# Sheet_2.net
KiCad netlist of a schematic drawn in EasyEDA
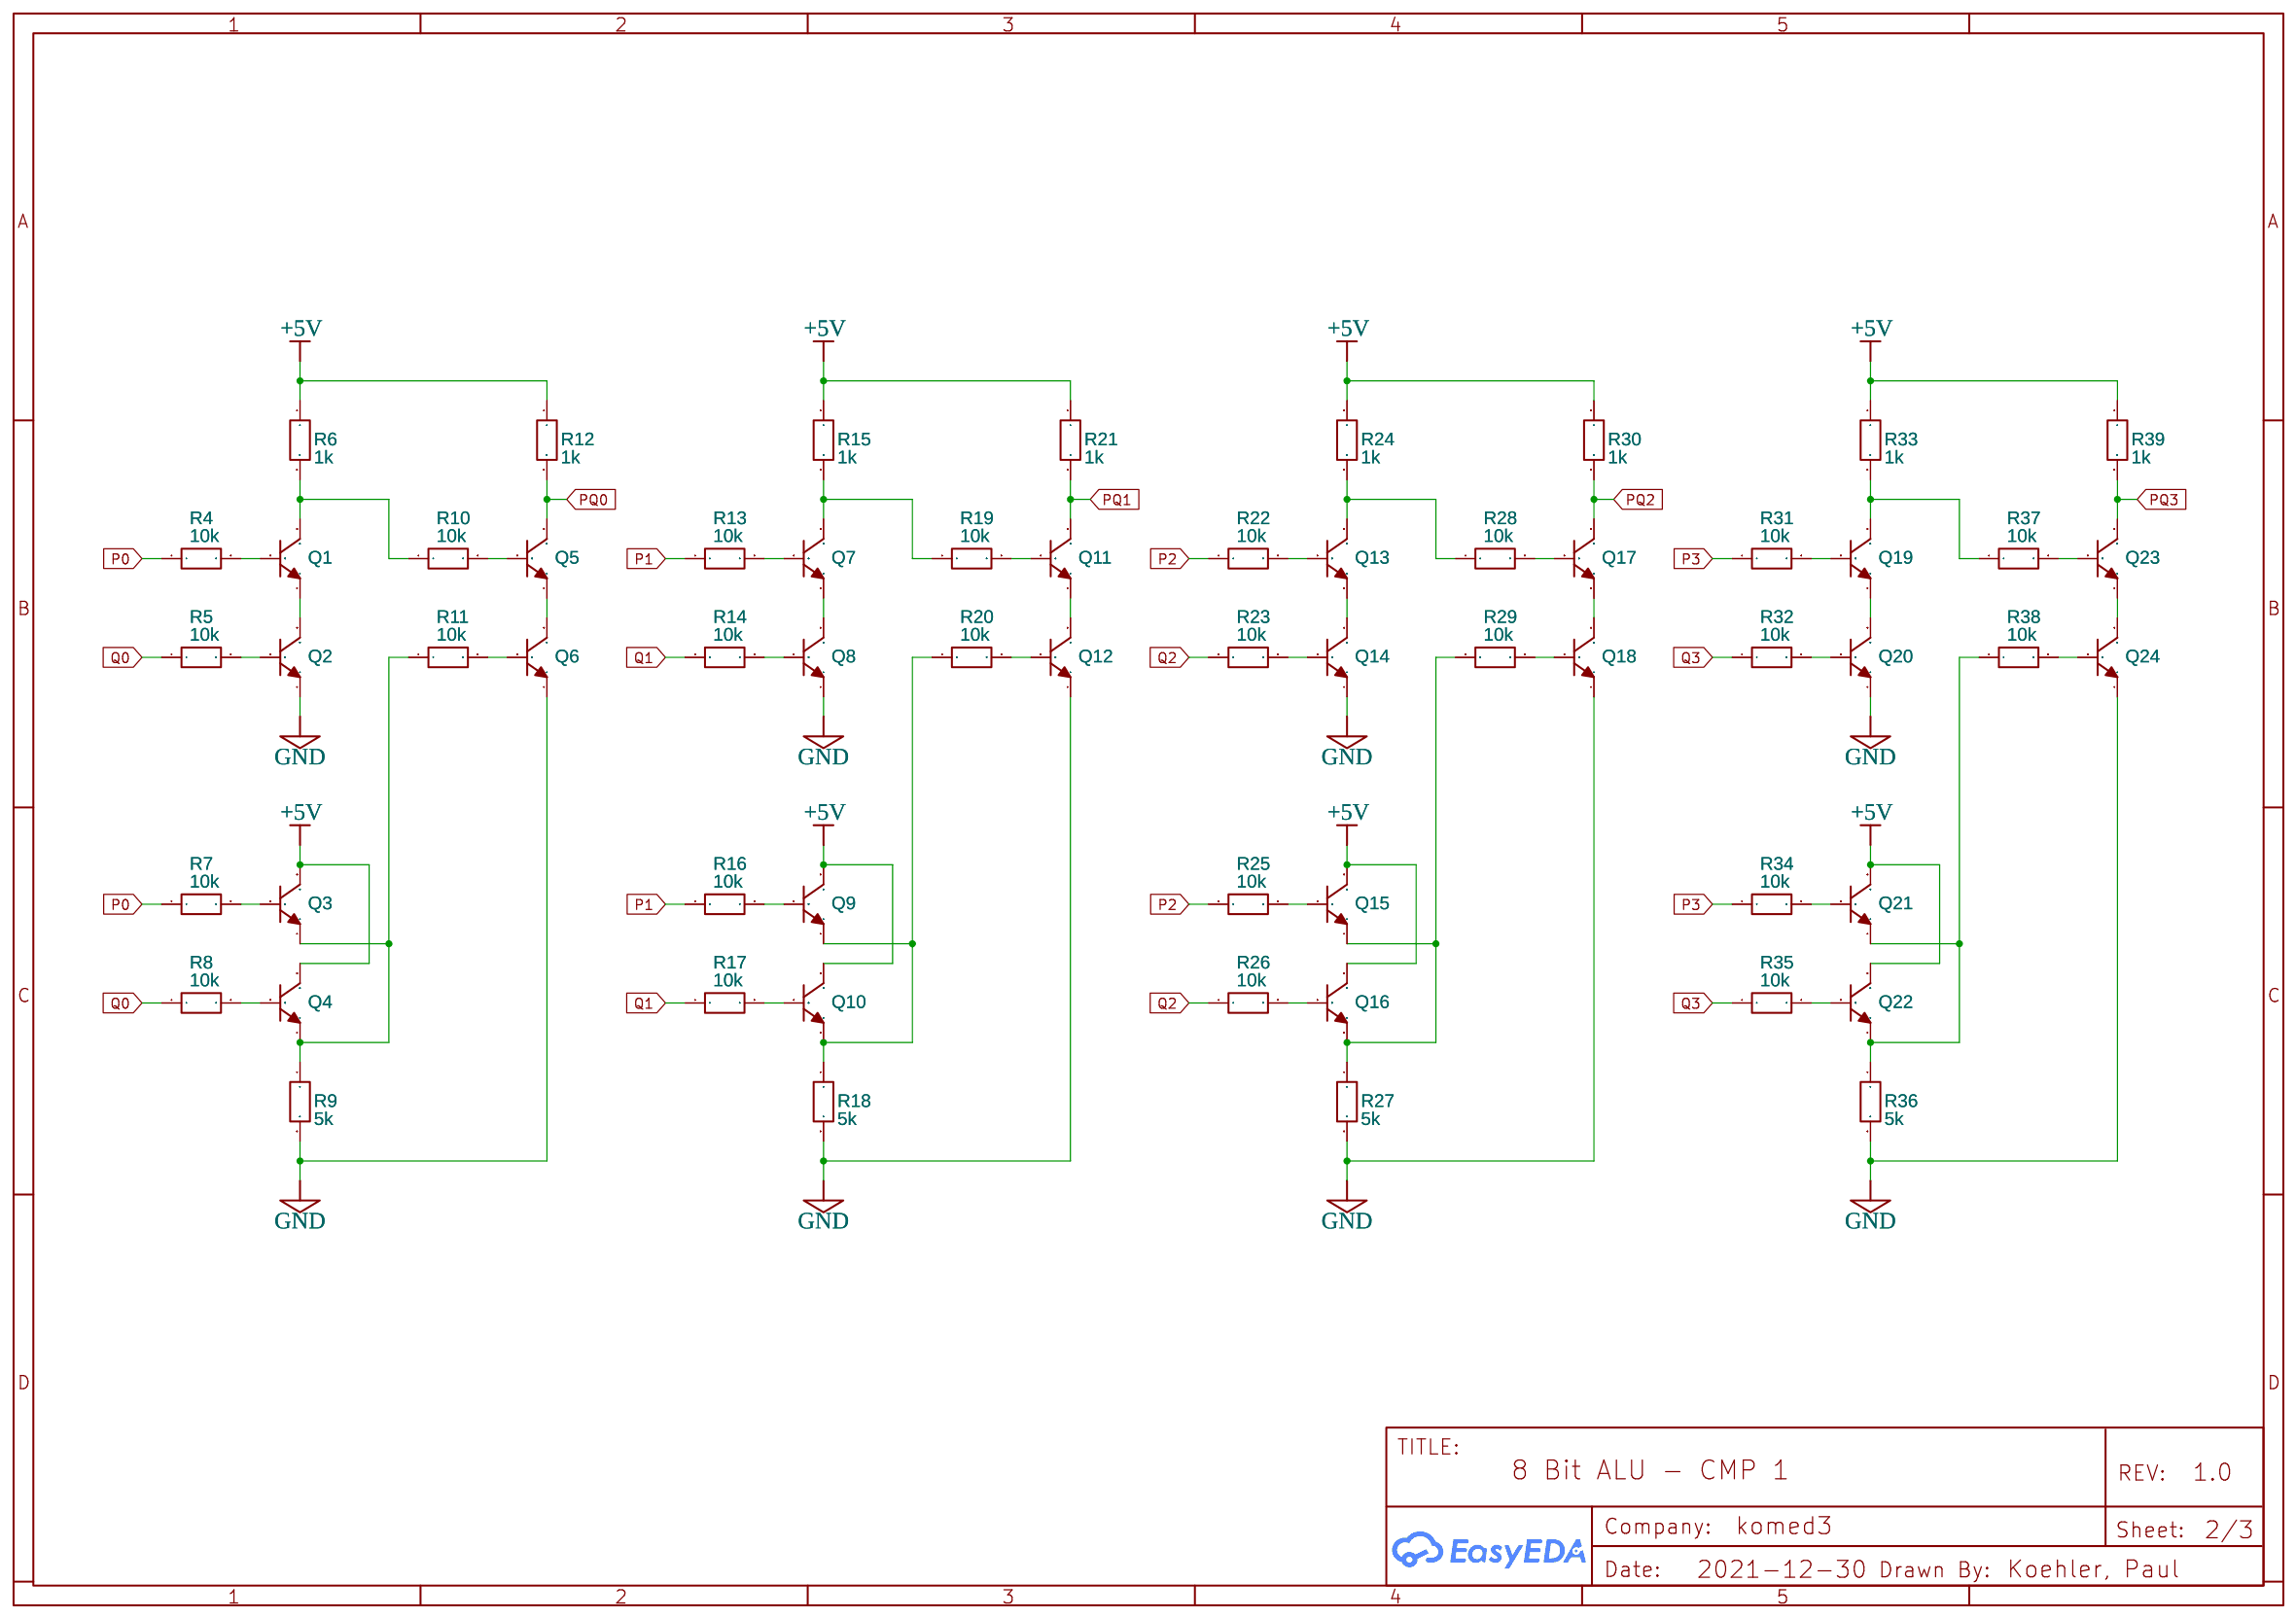
[diagram p0: schematic sheet]

(export (version "E")
  (design (tool "Eeschema 10.0.6"))
  (components
    (comp (ref "Q1")
      (value "2N3904(TO-92)")
      (fields (field (name "BOM_Manufacturer Part") "2N3904") (field (name "BOM_Supplier Part") "C118538"))
      (libsource (lib "") (part "2N3904(TO-92)"))
    )
    (comp (ref "Q2")
      (value "2N3904(TO-92)")
      (fields (field (name "BOM_Manufacturer Part") "2N3904") (field (name "BOM_Supplier Part") "C118538"))
      (libsource (lib "") (part "2N3904(TO-92)"))
    )
    (comp (ref "Q3")
      (value "2N3904(TO-92)")
      (fields (field (name "BOM_Manufacturer Part") "2N3904") (field (name "BOM_Supplier Part") "C118538"))
      (libsource (lib "") (part "2N3904(TO-92)"))
    )
    (comp (ref "Q4")
      (value "2N3904(TO-92)")
      (fields (field (name "BOM_Manufacturer Part") "2N3904") (field (name "BOM_Supplier Part") "C118538"))
      (libsource (lib "") (part "2N3904(TO-92)"))
    )
    (comp (ref "Q5")
      (value "2N3904(TO-92)")
      (fields (field (name "BOM_Manufacturer Part") "2N3904") (field (name "BOM_Supplier Part") "C118538"))
      (libsource (lib "") (part "2N3904(TO-92)"))
    )
    (comp (ref "Q6")
      (value "2N3904(TO-92)")
      (fields (field (name "BOM_Manufacturer Part") "2N3904") (field (name "BOM_Supplier Part") "C118538"))
      (libsource (lib "") (part "2N3904(TO-92)"))
    )
    (comp (ref "Q7")
      (value "2N3904(TO-92)")
      (fields (field (name "BOM_Manufacturer Part") "2N3904") (field (name "BOM_Supplier Part") "C118538"))
      (libsource (lib "") (part "2N3904(TO-92)"))
    )
    (comp (ref "Q8")
      (value "2N3904(TO-92)")
      (fields (field (name "BOM_Manufacturer Part") "2N3904") (field (name "BOM_Supplier Part") "C118538"))
      (libsource (lib "") (part "2N3904(TO-92)"))
    )
    (comp (ref "Q9")
      (value "2N3904(TO-92)")
      (fields (field (name "BOM_Manufacturer Part") "2N3904") (field (name "BOM_Supplier Part") "C118538"))
      (libsource (lib "") (part "2N3904(TO-92)"))
    )
    (comp (ref "Q10")
      (value "2N3904(TO-92)")
      (fields (field (name "BOM_Manufacturer Part") "2N3904") (field (name "BOM_Supplier Part") "C118538"))
      (libsource (lib "") (part "2N3904(TO-92)"))
    )
    (comp (ref "Q11")
      (value "2N3904(TO-92)")
      (fields (field (name "BOM_Manufacturer Part") "2N3904") (field (name "BOM_Supplier Part") "C118538"))
      (libsource (lib "") (part "2N3904(TO-92)"))
    )
    (comp (ref "Q12")
      (value "2N3904(TO-92)")
      (fields (field (name "BOM_Manufacturer Part") "2N3904") (field (name "BOM_Supplier Part") "C118538"))
      (libsource (lib "") (part "2N3904(TO-92)"))
    )
    (comp (ref "Q13")
      (value "2N3904(TO-92)")
      (fields (field (name "BOM_Manufacturer Part") "2N3904") (field (name "BOM_Supplier Part") "C118538"))
      (libsource (lib "") (part "2N3904(TO-92)"))
    )
    (comp (ref "Q14")
      (value "2N3904(TO-92)")
      (fields (field (name "BOM_Manufacturer Part") "2N3904") (field (name "BOM_Supplier Part") "C118538"))
      (libsource (lib "") (part "2N3904(TO-92)"))
    )
    (comp (ref "Q15")
      (value "2N3904(TO-92)")
      (fields (field (name "BOM_Manufacturer Part") "2N3904") (field (name "BOM_Supplier Part") "C118538"))
      (libsource (lib "") (part "2N3904(TO-92)"))
    )
    (comp (ref "Q16")
      (value "2N3904(TO-92)")
      (fields (field (name "BOM_Manufacturer Part") "2N3904") (field (name "BOM_Supplier Part") "C118538"))
      (libsource (lib "") (part "2N3904(TO-92)"))
    )
    (comp (ref "Q17")
      (value "2N3904(TO-92)")
      (fields (field (name "BOM_Manufacturer Part") "2N3904") (field (name "BOM_Supplier Part") "C118538"))
      (libsource (lib "") (part "2N3904(TO-92)"))
    )
    (comp (ref "Q18")
      (value "2N3904(TO-92)")
      (fields (field (name "BOM_Manufacturer Part") "2N3904") (field (name "BOM_Supplier Part") "C118538"))
      (libsource (lib "") (part "2N3904(TO-92)"))
    )
    (comp (ref "Q19")
      (value "2N3904(TO-92)")
      (fields (field (name "BOM_Manufacturer Part") "2N3904") (field (name "BOM_Supplier Part") "C118538"))
      (libsource (lib "") (part "2N3904(TO-92)"))
    )
    (comp (ref "Q20")
      (value "2N3904(TO-92)")
      (fields (field (name "BOM_Manufacturer Part") "2N3904") (field (name "BOM_Supplier Part") "C118538"))
      (libsource (lib "") (part "2N3904(TO-92)"))
    )
    (comp (ref "Q21")
      (value "2N3904(TO-92)")
      (fields (field (name "BOM_Manufacturer Part") "2N3904") (field (name "BOM_Supplier Part") "C118538"))
      (libsource (lib "") (part "2N3904(TO-92)"))
    )
    (comp (ref "Q22")
      (value "2N3904(TO-92)")
      (fields (field (name "BOM_Manufacturer Part") "2N3904") (field (name "BOM_Supplier Part") "C118538"))
      (libsource (lib "") (part "2N3904(TO-92)"))
    )
    (comp (ref "Q23")
      (value "2N3904(TO-92)")
      (fields (field (name "BOM_Manufacturer Part") "2N3904") (field (name "BOM_Supplier Part") "C118538"))
      (libsource (lib "") (part "2N3904(TO-92)"))
    )
    (comp (ref "Q24")
      (value "2N3904(TO-92)")
      (fields (field (name "BOM_Manufacturer Part") "2N3904") (field (name "BOM_Supplier Part") "C118538"))
      (libsource (lib "") (part "2N3904(TO-92)"))
    )
    (comp (ref "R4") (value "10k") (libsource (lib "") (part "R_AXIAL-0.3_EU_1")))
    (comp (ref "R5") (value "10k") (libsource (lib "") (part "R_AXIAL-0.3_EU_1")))
    (comp (ref "R6") (value "1k") (libsource (lib "") (part "R_AXIAL-0.3_EU")))
    (comp (ref "R7") (value "10k") (libsource (lib "") (part "R_AXIAL-0.3_EU_1")))
    (comp (ref "R8") (value "10k") (libsource (lib "") (part "R_AXIAL-0.3_EU_1")))
    (comp (ref "R9") (value "5k") (libsource (lib "") (part "R_AXIAL-0.3_EU")))
    (comp (ref "R10") (value "10k") (libsource (lib "") (part "R_AXIAL-0.3_EU_1")))
    (comp (ref "R11") (value "10k") (libsource (lib "") (part "R_AXIAL-0.3_EU_1")))
    (comp (ref "R12") (value "1k") (libsource (lib "") (part "R_AXIAL-0.3_EU")))
    (comp (ref "R13") (value "10k") (libsource (lib "") (part "R_AXIAL-0.3_EU_1")))
    (comp (ref "R14") (value "10k") (libsource (lib "") (part "R_AXIAL-0.3_EU_1")))
    (comp (ref "R15") (value "1k") (libsource (lib "") (part "R_AXIAL-0.3_EU")))
    (comp (ref "R16") (value "10k") (libsource (lib "") (part "R_AXIAL-0.3_EU_1")))
    (comp (ref "R17") (value "10k") (libsource (lib "") (part "R_AXIAL-0.3_EU_1")))
    (comp (ref "R18") (value "5k") (libsource (lib "") (part "R_AXIAL-0.3_EU")))
    (comp (ref "R19") (value "10k") (libsource (lib "") (part "R_AXIAL-0.3_EU_1")))
    (comp (ref "R20") (value "10k") (libsource (lib "") (part "R_AXIAL-0.3_EU_1")))
    (comp (ref "R21") (value "1k") (libsource (lib "") (part "R_AXIAL-0.3_EU")))
    (comp (ref "R22") (value "10k") (libsource (lib "") (part "R_AXIAL-0.3_EU_1")))
    (comp (ref "R23") (value "10k") (libsource (lib "") (part "R_AXIAL-0.3_EU_1")))
    (comp (ref "R24") (value "1k") (libsource (lib "") (part "R_AXIAL-0.3_EU")))
    (comp (ref "R25") (value "10k") (libsource (lib "") (part "R_AXIAL-0.3_EU_1")))
    (comp (ref "R26") (value "10k") (libsource (lib "") (part "R_AXIAL-0.3_EU_1")))
    (comp (ref "R27") (value "5k") (libsource (lib "") (part "R_AXIAL-0.3_EU")))
    (comp (ref "R28") (value "10k") (libsource (lib "") (part "R_AXIAL-0.3_EU_1")))
    (comp (ref "R29") (value "10k") (libsource (lib "") (part "R_AXIAL-0.3_EU_1")))
    (comp (ref "R30") (value "1k") (libsource (lib "") (part "R_AXIAL-0.3_EU")))
    (comp (ref "R31") (value "10k") (libsource (lib "") (part "R_AXIAL-0.3_EU_1")))
    (comp (ref "R32") (value "10k") (libsource (lib "") (part "R_AXIAL-0.3_EU_1")))
    (comp (ref "R33") (value "1k") (libsource (lib "") (part "R_AXIAL-0.3_EU")))
    (comp (ref "R34") (value "10k") (libsource (lib "") (part "R_AXIAL-0.3_EU_1")))
    (comp (ref "R35") (value "10k") (libsource (lib "") (part "R_AXIAL-0.3_EU_1")))
    (comp (ref "R36") (value "5k") (libsource (lib "") (part "R_AXIAL-0.3_EU")))
    (comp (ref "R37") (value "10k") (libsource (lib "") (part "R_AXIAL-0.3_EU_1")))
    (comp (ref "R38") (value "10k") (libsource (lib "") (part "R_AXIAL-0.3_EU_1")))
    (comp (ref "R39") (value "1k") (libsource (lib "") (part "R_AXIAL-0.3_EU")))
  )
  (nets
    (net (code "1") (name "+5V") (class "Default")
      (node (ref "Q10") (pin "3") (pinfunction "C_3") (pintype "unspecified"))
      (node (ref "Q15") (pin "3") (pinfunction "C_3") (pintype "unspecified"))
      (node (ref "Q16") (pin "3") (pinfunction "C_3") (pintype "unspecified"))
      (node (ref "Q21") (pin "3") (pinfunction "C_3") (pintype "unspecified"))
      (node (ref "Q22") (pin "3") (pinfunction "C_3") (pintype "unspecified"))
      (node (ref "Q3") (pin "3") (pinfunction "C_3") (pintype "unspecified"))
      (node (ref "Q4") (pin "3") (pinfunction "C_3") (pintype "unspecified"))
      (node (ref "Q9") (pin "3") (pinfunction "C_3") (pintype "unspecified"))
      (node (ref "R12") (pin "1") (pinfunction "1_1") (pintype "unspecified"))
      (node (ref "R15") (pin "1") (pinfunction "1_1") (pintype "unspecified"))
      (node (ref "R21") (pin "1") (pinfunction "1_1") (pintype "unspecified"))
      (node (ref "R24") (pin "1") (pinfunction "1_1") (pintype "unspecified"))
      (node (ref "R30") (pin "1") (pinfunction "1_1") (pintype "unspecified"))
      (node (ref "R33") (pin "1") (pinfunction "1_1") (pintype "unspecified"))
      (node (ref "R39") (pin "1") (pinfunction "1_1") (pintype "unspecified"))
      (node (ref "R6") (pin "1") (pinfunction "1_1") (pintype "unspecified"))
    )
    (net (code "2") (name "GND") (class "Default")
      (node (ref "Q12") (pin "1") (pinfunction "E_1") (pintype "unspecified"))
      (node (ref "Q14") (pin "1") (pinfunction "E_1") (pintype "unspecified"))
      (node (ref "Q18") (pin "1") (pinfunction "E_1") (pintype "unspecified"))
      (node (ref "Q2") (pin "1") (pinfunction "E_1") (pintype "unspecified"))
      (node (ref "Q20") (pin "1") (pinfunction "E_1") (pintype "unspecified"))
      (node (ref "Q24") (pin "1") (pinfunction "E_1") (pintype "unspecified"))
      (node (ref "Q6") (pin "1") (pinfunction "E_1") (pintype "unspecified"))
      (node (ref "Q8") (pin "1") (pinfunction "E_1") (pintype "unspecified"))
      (node (ref "R18") (pin "2") (pinfunction "2_2") (pintype "unspecified"))
      (node (ref "R27") (pin "2") (pinfunction "2_2") (pintype "unspecified"))
      (node (ref "R36") (pin "2") (pinfunction "2_2") (pintype "unspecified"))
      (node (ref "R9") (pin "2") (pinfunction "2_2") (pintype "unspecified"))
    )
    (net (code "3") (name "Net-(Q1-B)") (class "Default")
      (node (ref "Q1") (pin "2") (pinfunction "B_2") (pintype "unspecified"))
      (node (ref "R4") (pin "2") (pinfunction "2_2") (pintype "unspecified"))
    )
    (net (code "4") (name "Net-(Q1-C)") (class "Default")
      (node (ref "Q1") (pin "3") (pinfunction "C_3") (pintype "unspecified"))
      (node (ref "R10") (pin "1") (pinfunction "1_1") (pintype "unspecified"))
      (node (ref "R6") (pin "2") (pinfunction "2_2") (pintype "unspecified"))
    )
    (net (code "5") (name "Net-(Q1-E)") (class "Default")
      (node (ref "Q1") (pin "1") (pinfunction "E_1") (pintype "unspecified"))
      (node (ref "Q2") (pin "3") (pinfunction "C_3") (pintype "unspecified"))
    )
    (net (code "6") (name "Net-(Q2-B)") (class "Default")
      (node (ref "Q2") (pin "2") (pinfunction "B_2") (pintype "unspecified"))
      (node (ref "R5") (pin "2") (pinfunction "2_2") (pintype "unspecified"))
    )
    (net (code "7") (name "Net-(Q3-B)") (class "Default")
      (node (ref "Q3") (pin "2") (pinfunction "B_2") (pintype "unspecified"))
      (node (ref "R7") (pin "2") (pinfunction "2_2") (pintype "unspecified"))
    )
    (net (code "8") (name "Net-(Q3-E)") (class "Default")
      (node (ref "Q3") (pin "1") (pinfunction "E_1") (pintype "unspecified"))
      (node (ref "Q4") (pin "1") (pinfunction "E_1") (pintype "unspecified"))
      (node (ref "R11") (pin "1") (pinfunction "1_1") (pintype "unspecified"))
      (node (ref "R9") (pin "1") (pinfunction "1_1") (pintype "unspecified"))
    )
    (net (code "9") (name "Net-(Q4-B)") (class "Default")
      (node (ref "Q4") (pin "2") (pinfunction "B_2") (pintype "unspecified"))
      (node (ref "R8") (pin "2") (pinfunction "2_2") (pintype "unspecified"))
    )
    (net (code "10") (name "Net-(Q5-B)") (class "Default")
      (node (ref "Q5") (pin "2") (pinfunction "B_2") (pintype "unspecified"))
      (node (ref "R10") (pin "2") (pinfunction "2_2") (pintype "unspecified"))
    )
    (net (code "11") (name "Net-(Q5-E)") (class "Default")
      (node (ref "Q5") (pin "1") (pinfunction "E_1") (pintype "unspecified"))
      (node (ref "Q6") (pin "3") (pinfunction "C_3") (pintype "unspecified"))
    )
    (net (code "12") (name "Net-(Q6-B)") (class "Default")
      (node (ref "Q6") (pin "2") (pinfunction "B_2") (pintype "unspecified"))
      (node (ref "R11") (pin "2") (pinfunction "2_2") (pintype "unspecified"))
    )
    (net (code "13") (name "Net-(Q7-B)") (class "Default")
      (node (ref "Q7") (pin "2") (pinfunction "B_2") (pintype "unspecified"))
      (node (ref "R13") (pin "2") (pinfunction "2_2") (pintype "unspecified"))
    )
    (net (code "14") (name "Net-(Q7-C)") (class "Default")
      (node (ref "Q7") (pin "3") (pinfunction "C_3") (pintype "unspecified"))
      (node (ref "R15") (pin "2") (pinfunction "2_2") (pintype "unspecified"))
      (node (ref "R19") (pin "1") (pinfunction "1_1") (pintype "unspecified"))
    )
    (net (code "15") (name "Net-(Q7-E)") (class "Default")
      (node (ref "Q7") (pin "1") (pinfunction "E_1") (pintype "unspecified"))
      (node (ref "Q8") (pin "3") (pinfunction "C_3") (pintype "unspecified"))
    )
    (net (code "16") (name "Net-(Q8-B)") (class "Default")
      (node (ref "Q8") (pin "2") (pinfunction "B_2") (pintype "unspecified"))
      (node (ref "R14") (pin "2") (pinfunction "2_2") (pintype "unspecified"))
    )
    (net (code "17") (name "Net-(Q9-B)") (class "Default")
      (node (ref "Q9") (pin "2") (pinfunction "B_2") (pintype "unspecified"))
      (node (ref "R16") (pin "2") (pinfunction "2_2") (pintype "unspecified"))
    )
    (net (code "18") (name "Net-(Q10-B)") (class "Default")
      (node (ref "Q10") (pin "2") (pinfunction "B_2") (pintype "unspecified"))
      (node (ref "R17") (pin "2") (pinfunction "2_2") (pintype "unspecified"))
    )
    (net (code "19") (name "Net-(Q10-E)") (class "Default")
      (node (ref "Q10") (pin "1") (pinfunction "E_1") (pintype "unspecified"))
      (node (ref "Q9") (pin "1") (pinfunction "E_1") (pintype "unspecified"))
      (node (ref "R18") (pin "1") (pinfunction "1_1") (pintype "unspecified"))
      (node (ref "R20") (pin "1") (pinfunction "1_1") (pintype "unspecified"))
    )
    (net (code "20") (name "Net-(Q11-B)") (class "Default")
      (node (ref "Q11") (pin "2") (pinfunction "B_2") (pintype "unspecified"))
      (node (ref "R19") (pin "2") (pinfunction "2_2") (pintype "unspecified"))
    )
    (net (code "21") (name "Net-(Q11-E)") (class "Default")
      (node (ref "Q11") (pin "1") (pinfunction "E_1") (pintype "unspecified"))
      (node (ref "Q12") (pin "3") (pinfunction "C_3") (pintype "unspecified"))
    )
    (net (code "22") (name "Net-(Q12-B)") (class "Default")
      (node (ref "Q12") (pin "2") (pinfunction "B_2") (pintype "unspecified"))
      (node (ref "R20") (pin "2") (pinfunction "2_2") (pintype "unspecified"))
    )
    (net (code "23") (name "Net-(Q13-B)") (class "Default")
      (node (ref "Q13") (pin "2") (pinfunction "B_2") (pintype "unspecified"))
      (node (ref "R22") (pin "2") (pinfunction "2_2") (pintype "unspecified"))
    )
    (net (code "24") (name "Net-(Q13-C)") (class "Default")
      (node (ref "Q13") (pin "3") (pinfunction "C_3") (pintype "unspecified"))
      (node (ref "R24") (pin "2") (pinfunction "2_2") (pintype "unspecified"))
      (node (ref "R28") (pin "1") (pinfunction "1_1") (pintype "unspecified"))
    )
    (net (code "25") (name "Net-(Q13-E)") (class "Default")
      (node (ref "Q13") (pin "1") (pinfunction "E_1") (pintype "unspecified"))
      (node (ref "Q14") (pin "3") (pinfunction "C_3") (pintype "unspecified"))
    )
    (net (code "26") (name "Net-(Q14-B)") (class "Default")
      (node (ref "Q14") (pin "2") (pinfunction "B_2") (pintype "unspecified"))
      (node (ref "R23") (pin "2") (pinfunction "2_2") (pintype "unspecified"))
    )
    (net (code "27") (name "Net-(Q15-B)") (class "Default")
      (node (ref "Q15") (pin "2") (pinfunction "B_2") (pintype "unspecified"))
      (node (ref "R25") (pin "2") (pinfunction "2_2") (pintype "unspecified"))
    )
    (net (code "28") (name "Net-(Q15-E)") (class "Default")
      (node (ref "Q15") (pin "1") (pinfunction "E_1") (pintype "unspecified"))
      (node (ref "Q16") (pin "1") (pinfunction "E_1") (pintype "unspecified"))
      (node (ref "R27") (pin "1") (pinfunction "1_1") (pintype "unspecified"))
      (node (ref "R29") (pin "1") (pinfunction "1_1") (pintype "unspecified"))
    )
    (net (code "29") (name "Net-(Q16-B)") (class "Default")
      (node (ref "Q16") (pin "2") (pinfunction "B_2") (pintype "unspecified"))
      (node (ref "R26") (pin "2") (pinfunction "2_2") (pintype "unspecified"))
    )
    (net (code "30") (name "Net-(Q17-B)") (class "Default")
      (node (ref "Q17") (pin "2") (pinfunction "B_2") (pintype "unspecified"))
      (node (ref "R28") (pin "2") (pinfunction "2_2") (pintype "unspecified"))
    )
    (net (code "31") (name "Net-(Q17-E)") (class "Default")
      (node (ref "Q17") (pin "1") (pinfunction "E_1") (pintype "unspecified"))
      (node (ref "Q18") (pin "3") (pinfunction "C_3") (pintype "unspecified"))
    )
    (net (code "32") (name "Net-(Q18-B)") (class "Default")
      (node (ref "Q18") (pin "2") (pinfunction "B_2") (pintype "unspecified"))
      (node (ref "R29") (pin "2") (pinfunction "2_2") (pintype "unspecified"))
    )
    (net (code "33") (name "Net-(Q19-B)") (class "Default")
      (node (ref "Q19") (pin "2") (pinfunction "B_2") (pintype "unspecified"))
      (node (ref "R31") (pin "2") (pinfunction "2_2") (pintype "unspecified"))
    )
    (net (code "34") (name "Net-(Q19-C)") (class "Default")
      (node (ref "Q19") (pin "3") (pinfunction "C_3") (pintype "unspecified"))
      (node (ref "R33") (pin "2") (pinfunction "2_2") (pintype "unspecified"))
      (node (ref "R37") (pin "1") (pinfunction "1_1") (pintype "unspecified"))
    )
    (net (code "35") (name "Net-(Q19-E)") (class "Default")
      (node (ref "Q19") (pin "1") (pinfunction "E_1") (pintype "unspecified"))
      (node (ref "Q20") (pin "3") (pinfunction "C_3") (pintype "unspecified"))
    )
    (net (code "36") (name "Net-(Q20-B)") (class "Default")
      (node (ref "Q20") (pin "2") (pinfunction "B_2") (pintype "unspecified"))
      (node (ref "R32") (pin "2") (pinfunction "2_2") (pintype "unspecified"))
    )
    (net (code "37") (name "Net-(Q21-B)") (class "Default")
      (node (ref "Q21") (pin "2") (pinfunction "B_2") (pintype "unspecified"))
      (node (ref "R34") (pin "2") (pinfunction "2_2") (pintype "unspecified"))
    )
    (net (code "38") (name "Net-(Q21-E)") (class "Default")
      (node (ref "Q21") (pin "1") (pinfunction "E_1") (pintype "unspecified"))
      (node (ref "Q22") (pin "1") (pinfunction "E_1") (pintype "unspecified"))
      (node (ref "R36") (pin "1") (pinfunction "1_1") (pintype "unspecified"))
      (node (ref "R38") (pin "1") (pinfunction "1_1") (pintype "unspecified"))
    )
    (net (code "39") (name "Net-(Q22-B)") (class "Default")
      (node (ref "Q22") (pin "2") (pinfunction "B_2") (pintype "unspecified"))
      (node (ref "R35") (pin "2") (pinfunction "2_2") (pintype "unspecified"))
    )
    (net (code "40") (name "Net-(Q23-B)") (class "Default")
      (node (ref "Q23") (pin "2") (pinfunction "B_2") (pintype "unspecified"))
      (node (ref "R37") (pin "2") (pinfunction "2_2") (pintype "unspecified"))
    )
    (net (code "41") (name "Net-(Q23-E)") (class "Default")
      (node (ref "Q23") (pin "1") (pinfunction "E_1") (pintype "unspecified"))
      (node (ref "Q24") (pin "3") (pinfunction "C_3") (pintype "unspecified"))
    )
    (net (code "42") (name "Net-(Q24-B)") (class "Default")
      (node (ref "Q24") (pin "2") (pinfunction "B_2") (pintype "unspecified"))
      (node (ref "R38") (pin "2") (pinfunction "2_2") (pintype "unspecified"))
    )
    (net (code "43") (name "P0") (class "Default")
      (node (ref "R4") (pin "1") (pinfunction "1_1") (pintype "unspecified"))
      (node (ref "R7") (pin "1") (pinfunction "1_1") (pintype "unspecified"))
    )
    (net (code "44") (name "P1") (class "Default")
      (node (ref "R13") (pin "1") (pinfunction "1_1") (pintype "unspecified"))
      (node (ref "R16") (pin "1") (pinfunction "1_1") (pintype "unspecified"))
    )
    (net (code "45") (name "P2") (class "Default")
      (node (ref "R22") (pin "1") (pinfunction "1_1") (pintype "unspecified"))
      (node (ref "R25") (pin "1") (pinfunction "1_1") (pintype "unspecified"))
    )
    (net (code "46") (name "P3") (class "Default")
      (node (ref "R31") (pin "1") (pinfunction "1_1") (pintype "unspecified"))
      (node (ref "R34") (pin "1") (pinfunction "1_1") (pintype "unspecified"))
    )
    (net (code "47") (name "PQ0") (class "Default")
      (node (ref "Q5") (pin "3") (pinfunction "C_3") (pintype "unspecified"))
      (node (ref "R12") (pin "2") (pinfunction "2_2") (pintype "unspecified"))
    )
    (net (code "48") (name "PQ1") (class "Default")
      (node (ref "Q11") (pin "3") (pinfunction "C_3") (pintype "unspecified"))
      (node (ref "R21") (pin "2") (pinfunction "2_2") (pintype "unspecified"))
    )
    (net (code "49") (name "PQ2") (class "Default")
      (node (ref "Q17") (pin "3") (pinfunction "C_3") (pintype "unspecified"))
      (node (ref "R30") (pin "2") (pinfunction "2_2") (pintype "unspecified"))
    )
    (net (code "50") (name "PQ3") (class "Default")
      (node (ref "Q23") (pin "3") (pinfunction "C_3") (pintype "unspecified"))
      (node (ref "R39") (pin "2") (pinfunction "2_2") (pintype "unspecified"))
    )
    (net (code "51") (name "Q0") (class "Default")
      (node (ref "R5") (pin "1") (pinfunction "1_1") (pintype "unspecified"))
      (node (ref "R8") (pin "1") (pinfunction "1_1") (pintype "unspecified"))
    )
    (net (code "52") (name "Q1") (class "Default")
      (node (ref "R14") (pin "1") (pinfunction "1_1") (pintype "unspecified"))
      (node (ref "R17") (pin "1") (pinfunction "1_1") (pintype "unspecified"))
    )
    (net (code "53") (name "Q2") (class "Default")
      (node (ref "R23") (pin "1") (pinfunction "1_1") (pintype "unspecified"))
      (node (ref "R26") (pin "1") (pinfunction "1_1") (pintype "unspecified"))
    )
    (net (code "54") (name "Q3") (class "Default")
      (node (ref "R32") (pin "1") (pinfunction "1_1") (pintype "unspecified"))
      (node (ref "R35") (pin "1") (pinfunction "1_1") (pintype "unspecified"))
    )
  )
)
